# dp2usbc.net
KiCad netlist of a schematic drawn in EAGLE
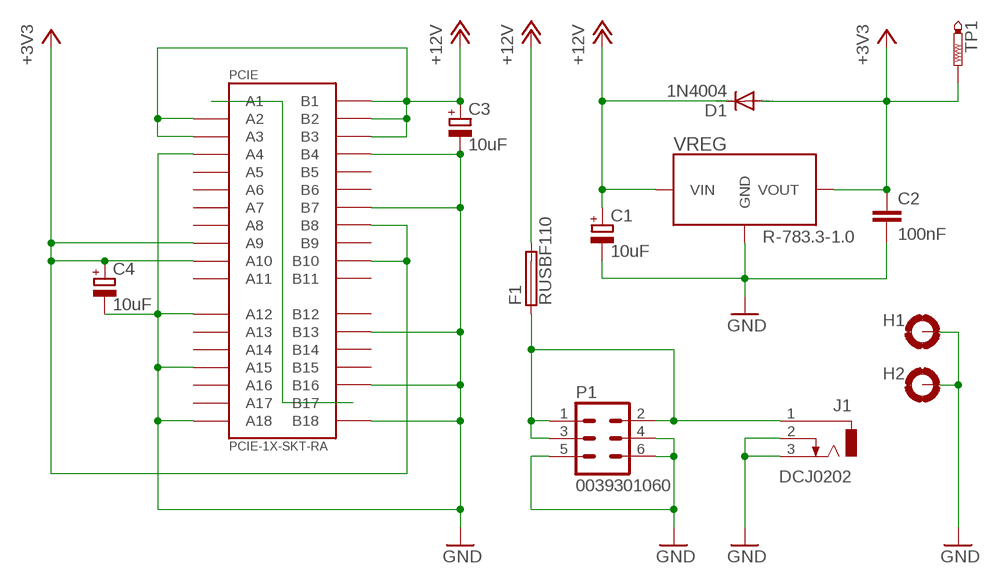
[diagram p0: schematic, sheet 1]

(export (version "E")
  (design (tool "Eeschema 10.0.6"))
  (components
    (comp (ref "C1")
      (value "10uF")
      (footprint "eagle-import:E1,8-4")
      (libsource (lib "eagle-import") (part "CPOL-EUE1.8-4"))
    )
    (comp (ref "C2")
      (value "100nF")
      (footprint "eagle-import:C025-024X044")
      (libsource (lib "eagle-import") (part "C-EU025-024X044"))
    )
    (comp (ref "C3")
      (value "10uF")
      (footprint "eagle-import:E1,8-4")
      (libsource (lib "eagle-import") (part "CPOL-EUE1.8-4"))
    )
    (comp (ref "C4")
      (value "10uF")
      (footprint "eagle-import:E1,8-4")
      (libsource (lib "eagle-import") (part "CPOL-EUE1.8-4"))
    )
    (comp (ref "D1")
      (value "1N4004")
      (footprint "eagle-import:DO41-10")
      (libsource (lib "eagle-import") (part "1N4004"))
    )
    (comp (ref "F1")
      (value "RUSBF110")
      (footprint "eagle-import:LITTLEFUSE")
      (fields (field (name "MF") "Littlefuse"))
      (libsource (lib "eagle-import") (part "LITTLEFUSE"))
    )
    (comp (ref "H1")
      (value "MOUNT-PAD-ROUND3.2")
      (footprint "eagle-import:3,2-PAD")
      (libsource (lib "eagle-import") (part "MOUNT-PAD-ROUND3.2"))
    )
    (comp (ref "H2")
      (value "MOUNT-PAD-ROUND3.2")
      (footprint "eagle-import:3,2-PAD")
      (libsource (lib "eagle-import") (part "MOUNT-PAD-ROUND3.2"))
    )
    (comp (ref "J1")
      (value "DCJ0202")
      (footprint "eagle-import:DCJ0202")
      (libsource (lib "eagle-import") (part "DCJ0202"))
    )
    (comp (ref "P1")
      (value "0039301060")
      (footprint "eagle-import:0039301060")
      (libsource (lib "eagle-import") (part "0039301060"))
    )
    (comp (ref "PCIE")
      (value "PCIE-1X-SKT-RA")
      (footprint "eagle-import:PCIE-1X-SKT-RA")
      (fields (field (name "MF") "ERNI Electronics") (field (name "MPN") "009000"))
      (libsource (lib "eagle-import") (part "PCIE-1X-SKT-RA"))
    )
    (comp (ref "TP1")
      (value "PTR1B1,27")
      (footprint "eagle-import:B1,27")
      (libsource (lib "eagle-import") (part "PTR1B1,27"))
    )
    (comp (ref "VREG")
      (value "R-783.3-1.0")
      (footprint "eagle-import:VREG-RECOM-78_")
      (libsource (lib "eagle-import") (part "VREG-RECOM-78"))
    )
  )
  (nets
    (net (code "1") (name "+3V3") (class "Default")
      (node (ref "C2") (pin "1") (pinfunction "1_1") (pintype "passive"))
      (node (ref "C4") (pin "+") (pinfunction "+_+") (pintype "passive"))
      (node (ref "D1") (pin "A") (pinfunction "A_A") (pintype "passive"))
      (node (ref "PCIE") (pin "A10") (pinfunction "A10_A10") (pintype "power_in"))
      (node (ref "PCIE") (pin "A9") (pinfunction "A9_A9") (pintype "power_in"))
      (node (ref "PCIE") (pin "B10") (pinfunction "B10_B10") (pintype "power_in"))
      (node (ref "PCIE") (pin "B8") (pinfunction "B8_B8") (pintype "power_in"))
      (node (ref "TP1") (pin "TP") (pinfunction "TP_TP") (pintype "input"))
      (node (ref "VREG") (pin "VOUT") (pinfunction "VOUT_VOUT") (pintype "power_in"))
    )
    (net (code "2") (name "+12V") (class "Default")
      (node (ref "C1") (pin "+") (pinfunction "+_+") (pintype "passive"))
      (node (ref "C3") (pin "+") (pinfunction "+_+") (pintype "passive"))
      (node (ref "D1") (pin "C") (pinfunction "C_C") (pintype "passive"))
      (node (ref "F1") (pin "2") (pinfunction "2_2") (pintype "passive"))
      (node (ref "PCIE") (pin "A2") (pinfunction "A2_A2") (pintype "power_in"))
      (node (ref "PCIE") (pin "A3") (pinfunction "A3_A3") (pintype "power_in"))
      (node (ref "PCIE") (pin "B1") (pinfunction "B1_B1") (pintype "power_in"))
      (node (ref "PCIE") (pin "B2") (pinfunction "B2_B2") (pintype "power_in"))
      (node (ref "PCIE") (pin "B3") (pinfunction "B3_B3") (pintype "power_in"))
      (node (ref "VREG") (pin "VIN") (pinfunction "VIN_VIN") (pintype "power_in"))
    )
    (net (code "3") (name "/B11") (class "Default")
      (node (ref "PCIE") (pin "B11") (pinfunction "B11_B11") (pintype "power_in"))
    )
    (net (code "4") (name "GND") (class "Default")
      (node (ref "C1") (pin "-") (pinfunction "-_-") (pintype "passive"))
      (node (ref "C2") (pin "2") (pinfunction "2_2") (pintype "passive"))
      (node (ref "C3") (pin "-") (pinfunction "-_-") (pintype "passive"))
      (node (ref "C4") (pin "-") (pinfunction "-_-") (pintype "passive"))
      (node (ref "H1") (pin "B3,2") (pinfunction "MOUNT_B3,2") (pintype "passive"))
      (node (ref "H2") (pin "B3,2") (pinfunction "MOUNT_B3,2") (pintype "passive"))
      (node (ref "J1") (pin "2") (pinfunction "2_2") (pintype "passive"))
      (node (ref "J1") (pin "3") (pinfunction "3_3") (pintype "passive"))
      (node (ref "P1") (pin "4") (pinfunction "4_4") (pintype "passive"))
      (node (ref "P1") (pin "5") (pinfunction "5_5") (pintype "passive"))
      (node (ref "P1") (pin "6") (pinfunction "6_6") (pintype "passive"))
      (node (ref "PCIE") (pin "A12") (pinfunction "A12_A12") (pintype "power_in"))
      (node (ref "PCIE") (pin "A15") (pinfunction "A15_A15") (pintype "power_in"))
      (node (ref "PCIE") (pin "A18") (pinfunction "A18_A18") (pintype "power_in"))
      (node (ref "PCIE") (pin "A4") (pinfunction "A4_A4") (pintype "power_in"))
      (node (ref "PCIE") (pin "B13") (pinfunction "B13_B13") (pintype "power_in"))
      (node (ref "PCIE") (pin "B16") (pinfunction "B16_B16") (pintype "power_in"))
      (node (ref "PCIE") (pin "B18") (pinfunction "B18_B18") (pintype "power_in"))
      (node (ref "PCIE") (pin "B4") (pinfunction "B4_B4") (pintype "power_in"))
      (node (ref "PCIE") (pin "B7") (pinfunction "B7_B7") (pintype "power_in"))
      (node (ref "VREG") (pin "GND") (pinfunction "GND_GND") (pintype "power_in"))
    )
    (net (code "5") (name "Net-(F1-Pad1)") (class "Default")
      (node (ref "F1") (pin "1") (pinfunction "1_1") (pintype "passive"))
      (node (ref "J1") (pin "1") (pinfunction "1_1") (pintype "passive"))
      (node (ref "P1") (pin "1") (pinfunction "1_1") (pintype "passive"))
      (node (ref "P1") (pin "2") (pinfunction "2_2") (pintype "passive"))
      (node (ref "P1") (pin "3") (pinfunction "3_3") (pintype "passive"))
    )
    (net (code "6") (name "Net-(PCIE-PadA1)") (class "Default")
      (node (ref "PCIE") (pin "A1") (pinfunction "A1_A1") (pintype "bidirectional"))
      (node (ref "PCIE") (pin "B17") (pinfunction "B17_B17") (pintype "bidirectional"))
    )
    (net (code "7") (name "unconnected-(PCIE-PadA5)") (class "Default")
      (node (ref "PCIE") (pin "A5") (pinfunction "A5_A5") (pintype "bidirectional"))
    )
    (net (code "8") (name "unconnected-(PCIE-PadA6)") (class "Default")
      (node (ref "PCIE") (pin "A6") (pinfunction "A6_A6") (pintype "bidirectional"))
    )
    (net (code "9") (name "unconnected-(PCIE-PadA7)") (class "Default")
      (node (ref "PCIE") (pin "A7") (pinfunction "A7_A7") (pintype "bidirectional"))
    )
    (net (code "10") (name "unconnected-(PCIE-PadA8)") (class "Default")
      (node (ref "PCIE") (pin "A8") (pinfunction "A8_A8") (pintype "bidirectional"))
    )
    (net (code "11") (name "unconnected-(PCIE-PadA11)") (class "Default")
      (node (ref "PCIE") (pin "A11") (pinfunction "A11_A11") (pintype "bidirectional"))
    )
    (net (code "12") (name "unconnected-(PCIE-PadA13)") (class "Default")
      (node (ref "PCIE") (pin "A13") (pinfunction "A13_A13") (pintype "bidirectional"))
    )
    (net (code "13") (name "unconnected-(PCIE-PadA14)") (class "Default")
      (node (ref "PCIE") (pin "A14") (pinfunction "A14_A14") (pintype "bidirectional"))
    )
    (net (code "14") (name "unconnected-(PCIE-PadA16)") (class "Default")
      (node (ref "PCIE") (pin "A16") (pinfunction "A16_A16") (pintype "bidirectional"))
    )
    (net (code "15") (name "unconnected-(PCIE-PadA17)") (class "Default")
      (node (ref "PCIE") (pin "A17") (pinfunction "A17_A17") (pintype "bidirectional"))
    )
    (net (code "16") (name "unconnected-(PCIE-PadB5)") (class "Default")
      (node (ref "PCIE") (pin "B5") (pinfunction "B5_B5") (pintype "bidirectional"))
    )
    (net (code "17") (name "unconnected-(PCIE-PadB6)") (class "Default")
      (node (ref "PCIE") (pin "B6") (pinfunction "B6_B6") (pintype "bidirectional"))
    )
    (net (code "18") (name "unconnected-(PCIE-PadB9)") (class "Default")
      (node (ref "PCIE") (pin "B9") (pinfunction "B9_B9") (pintype "bidirectional"))
    )
    (net (code "19") (name "unconnected-(PCIE-PadB12)") (class "Default")
      (node (ref "PCIE") (pin "B12") (pinfunction "B12_B12") (pintype "bidirectional"))
    )
    (net (code "20") (name "unconnected-(PCIE-PadB14)") (class "Default")
      (node (ref "PCIE") (pin "B14") (pinfunction "B14_B14") (pintype "bidirectional"))
    )
    (net (code "21") (name "unconnected-(PCIE-PadB15)") (class "Default")
      (node (ref "PCIE") (pin "B15") (pinfunction "B15_B15") (pintype "bidirectional"))
    )
  )
)
